# DAC_and_amp.net
KiCad netlist of a schematic drawn in Altium Designer
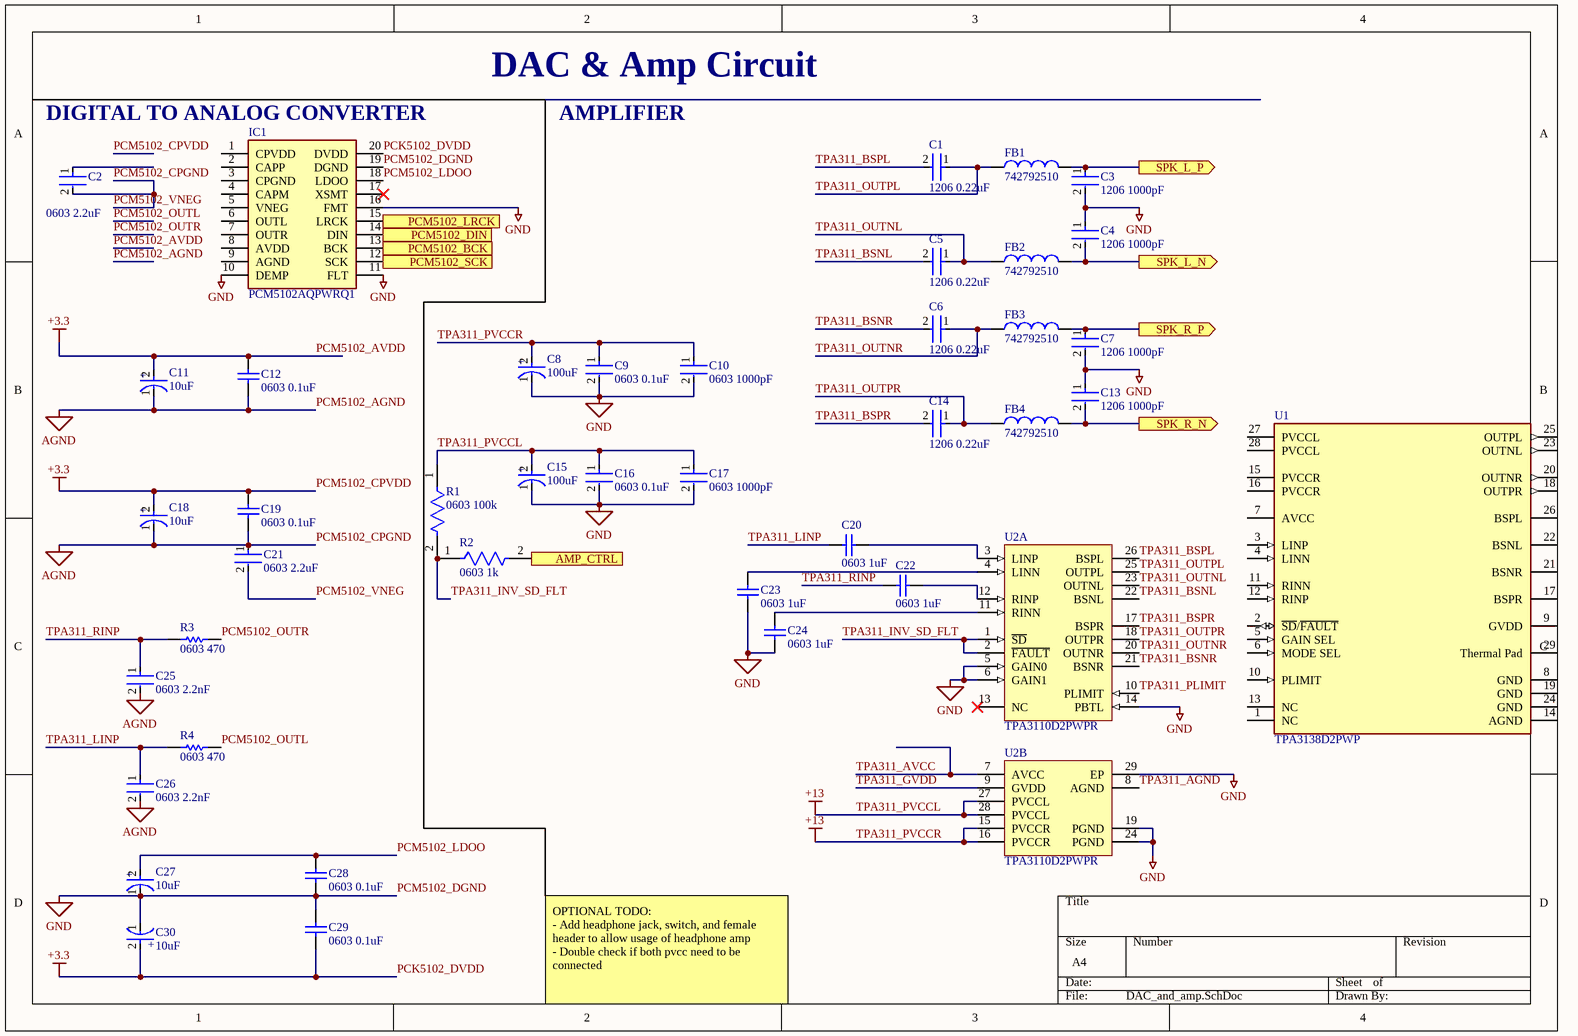
[diagram p0: DAC_and_amp.SchDoc]

(export (version "E")
  (design (tool "Eeschema 10.0.6"))
  (components
    (comp (ref "C1")
      (value "1206 0.22uF")
      (footprint "FP-C1206C-EB-MFG")
      (description "CAP CER 0.22UF 50V X7R 1206")
      (fields
        (field (name "OCTOPART") "https://octopart.com/c1206c224k5ractu-kemet-99129")
        (field (name "MANUFACTURER PART NUMBER") "C1206C224K5RACTU")
      )
      (libsource (lib "Altium Content Vault") (part "b4654b650e69147ec39a6b967a45e02"))
    )
    (comp (ref "C2")
      (value "0603 2.2uF")
      (footprint "FP-GRM188-0_1-e0_2_0_5-MFG")
      (description "Chip Multilayer Ceramic Capacitors for General Purpose, 0603, 2.2uF, X7R, 15%, 10%, 10V")
      (fields (field (name "VOLTAGE") "10V") (field (name "TOLERANCE") "10%"))
      (libsource (lib "Altium Content Vault") (part "11868f565c42a9108669ba33697ecf6"))
    )
    (comp (ref "C3")
      (value "1206 1000pF")
      (footprint "FP-C1206C-EB-MFG")
      (description "CAP CER 100PF 100V C0G/NP0 1206")
      (fields (field (name "MANUFACTURER") "KEMET") (field (name "TOLERANCE") "0.05"))
      (libsource (lib "Altium Content Vault") (part "b4654b650e69147ec39a6b967a45e02"))
    )
    (comp (ref "C4")
      (value "1206 1000pF")
      (footprint "FP-C1206C-EB-MFG")
      (description "CAP CER 100PF 100V C0G/NP0 1206")
      (fields (field (name "MANUFACTURER") "KEMET") (field (name "TOLERANCE") "0.05"))
      (libsource (lib "Altium Content Vault") (part "b4654b650e69147ec39a6b967a45e02"))
    )
    (comp (ref "C5")
      (value "1206 0.22uF")
      (footprint "FP-C1206C-EB-MFG")
      (description "CAP CER 0.22UF 50V X7R 1206")
      (fields
        (field (name "OCTOPART") "https://octopart.com/c1206c224k5ractu-kemet-99129")
        (field (name "MANUFACTURER PART NUMBER") "C1206C224K5RACTU")
      )
      (libsource (lib "Altium Content Vault") (part "b4654b650e69147ec39a6b967a45e02"))
    )
    (comp (ref "C6")
      (value "1206 0.22uF")
      (footprint "FP-C1206C-EB-MFG")
      (description "CAP CER 0.22UF 50V X7R 1206")
      (fields
        (field (name "OCTOPART") "https://octopart.com/c1206c224k5ractu-kemet-99129")
        (field (name "MANUFACTURER PART NUMBER") "C1206C224K5RACTU")
      )
      (libsource (lib "Altium Content Vault") (part "b4654b650e69147ec39a6b967a45e02"))
    )
    (comp (ref "C7")
      (value "1206 1000pF")
      (footprint "FP-C1206C-EB-MFG")
      (description "CAP CER 100PF 100V C0G/NP0 1206")
      (fields (field (name "MANUFACTURER") "KEMET") (field (name "TOLERANCE") "0.05"))
      (libsource (lib "Altium Content Vault") (part "b4654b650e69147ec39a6b967a45e02"))
    )
    (comp (ref "C8")
      (value "100uF")
      (footprint "FP-RAD-TH-D_8_0_5-L_11_5-MFG")
      (description "Aluminum Electrolytic Capacitors (Radial Lead Type) 100uF ±20% 50V")
      (fields (field (name "VOLTAGE") "50V") (field (name "TOLERANCE") "20%"))
      (libsource (lib "Altium Content Vault") (part "a00bbbee19879c290e62620ae7e47b1"))
    )
    (comp (ref "C9")
      (value "0603 0.1uF")
      (footprint "FP-C0603C-CF-MFG")
      (description "C0603 0.10 μF X7R 30ppm/°C 10.00% 25 V")
      (fields (field (name "MANUFACTURER PART NUMBER") "C0603C104K3RACTU"))
      (libsource (lib "Altium Content Vault") (part "b4654b650e69147ec39a6b967a45e02"))
    )
    (comp (ref "C10")
      (value "0603 1000pF")
      (footprint "FP-C0603C-CF-MFG")
      (description "C0603 1,000 pF C0G 30ppm/°C 5.00% 25 V")
      (fields (field (name "OCTOPART") "https://octopart.com/c0603c102j3gactu-kemet-8375722"))
      (libsource (lib "Altium Content Vault") (part "b4654b650e69147ec39a6b967a45e02"))
    )
    (comp (ref "C11")
      (value "10uF")
      (footprint "FP-35ZLH330MEFC10X12_5-MFG")
      (fields (field (name "TOLERANCE") "20%") (field (name "VOLTAGE") "35V"))
      (libsource (lib "Altium Content Vault") (part "a00bbbee19879c290e62620ae7e47b1"))
    )
    (comp (ref "C12")
      (value "0603 0.1uF")
      (footprint "CAPC1608X90X35ML10T15")
      (description "Chip Capacitor, 0.1 uF, +/- 10%, 50 V, -55 to 125 degC, 0603 (1608 Metric), RoHS, Tape and Reel")
      (fields (field (name "TOLERANCE") "10%") (field (name "VOLTAGE") "50V"))
      (libsource (lib "Altium Content Vault") (part "CAP-NP-2"))
    )
    (comp (ref "C13")
      (value "1206 1000pF")
      (footprint "FP-C1206C-EB-MFG")
      (description "CAP CER 100PF 100V C0G/NP0 1206")
      (fields (field (name "MANUFACTURER") "KEMET") (field (name "TOLERANCE") "0.05"))
      (libsource (lib "Altium Content Vault") (part "b4654b650e69147ec39a6b967a45e02"))
    )
    (comp (ref "C14")
      (value "1206 0.22uF")
      (footprint "FP-C1206C-EB-MFG")
      (description "CAP CER 0.22UF 50V X7R 1206")
      (fields
        (field (name "OCTOPART") "https://octopart.com/c1206c224k5ractu-kemet-99129")
        (field (name "MANUFACTURER PART NUMBER") "C1206C224K5RACTU")
      )
      (libsource (lib "Altium Content Vault") (part "b4654b650e69147ec39a6b967a45e02"))
    )
    (comp (ref "C15")
      (value "100uF")
      (footprint "FP-RAD-TH-D_8_0_5-L_11_5-MFG")
      (description "Aluminum Electrolytic Capacitors (Radial Lead Type) 100uF ±20% 50V")
      (fields (field (name "VOLTAGE") "50V") (field (name "TOLERANCE") "20%"))
      (libsource (lib "Altium Content Vault") (part "a00bbbee19879c290e62620ae7e47b1"))
    )
    (comp (ref "C16")
      (value "0603 0.1uF")
      (footprint "FP-C0603C-CF-MFG")
      (description "C0603 0.10 μF X7R 30ppm/°C 10.00% 25 V")
      (fields (field (name "MANUFACTURER PART NUMBER") "C0603C104K3RACTU"))
      (libsource (lib "Altium Content Vault") (part "b4654b650e69147ec39a6b967a45e02"))
    )
    (comp (ref "C17")
      (value "0603 1000pF")
      (footprint "FP-C0603C-CF-MFG")
      (description "C0603 1,000 pF C0G 30ppm/°C 5.00% 25 V")
      (fields (field (name "OCTOPART") "https://octopart.com/c0603c102j3gactu-kemet-8375722"))
      (libsource (lib "Altium Content Vault") (part "b4654b650e69147ec39a6b967a45e02"))
    )
    (comp (ref "C18")
      (value "10uF")
      (footprint "FP-35ZLH330MEFC10X12_5-MFG")
      (fields (field (name "TOLERANCE") "20%") (field (name "VOLTAGE") "35V"))
      (libsource (lib "Altium Content Vault") (part "a00bbbee19879c290e62620ae7e47b1"))
    )
    (comp (ref "C19")
      (value "0603 0.1uF")
      (footprint "CAPC1608X90X35ML10T15")
      (description "Chip Capacitor, 0.1 uF, +/- 10%, 50 V, -55 to 125 degC, 0603 (1608 Metric), RoHS, Tape and Reel")
      (fields (field (name "TOLERANCE") "10%") (field (name "VOLTAGE") "50V"))
      (libsource (lib "Altium Content Vault") (part "CAP-NP-2"))
    )
    (comp (ref "C20")
      (value "0603 1uF")
      (footprint "CAPC1608X87X35LL15T15")
      (fields (field (name "PART NUMBER") "C0603C105K3RACTU") (field (name "MANUFACTURER") "Kemet"))
      (libsource (lib "Altium Content Vault") (part "CAP"))
    )
    (comp (ref "C21")
      (value "0603 2.2uF")
      (footprint "FP-GRM188-0_1-e0_2_0_5-MFG")
      (description "Chip Multilayer Ceramic Capacitors for General Purpose, 0603, 2.2uF, X7R, 15%, 10%, 10V")
      (fields (field (name "VOLTAGE") "10V") (field (name "TOLERANCE") "10%"))
      (libsource (lib "Altium Content Vault") (part "11868f565c42a9108669ba33697ecf6"))
    )
    (comp (ref "C22")
      (value "0603 1uF")
      (footprint "CAPC1608X87X35LL15T15")
      (fields (field (name "PART NUMBER") "C0603C105K3RACTU") (field (name "MANUFACTURER") "Kemet"))
      (libsource (lib "Altium Content Vault") (part "CAP"))
    )
    (comp (ref "C23")
      (value "0603 1uF")
      (footprint "CAPC1608X87X35LL15T15")
      (fields (field (name "PART NUMBER") "C0603C105K3RACTU") (field (name "MANUFACTURER") "Kemet"))
      (libsource (lib "Altium Content Vault") (part "CAP"))
    )
    (comp (ref "C24")
      (value "0603 1uF")
      (footprint "CAPC1608X87X35LL15T15")
      (fields (field (name "PART NUMBER") "C0603C105K3RACTU") (field (name "MANUFACTURER") "Kemet"))
      (libsource (lib "Altium Content Vault") (part "CAP"))
    )
    (comp (ref "C25")
      (value "0603 2.2nF")
      (footprint "FP-GRM188-0_1-e0_2_0_5-MFG")
      (description "Chip Multilayer Ceramic Capacitors for General Purpose, 0603, 2200pF, C0G, 30ppm/°C, 5%, 50V")
      (fields (field (name "VOLTAGE") "50V") (field (name "TOLERANCE") "5%"))
      (libsource (lib "Altium Content Vault") (part "11868f565c42a9108669ba33697ecf6"))
    )
    (comp (ref "C26")
      (value "0603 2.2nF")
      (footprint "FP-GRM188-0_1-e0_2_0_5-MFG")
      (description "Chip Multilayer Ceramic Capacitors for General Purpose, 0603, 2200pF, C0G, 30ppm/°C, 5%, 50V")
      (fields (field (name "VOLTAGE") "50V") (field (name "TOLERANCE") "5%"))
      (libsource (lib "Altium Content Vault") (part "11868f565c42a9108669ba33697ecf6"))
    )
    (comp (ref "C27")
      (value "10uF")
      (footprint "FP-35ZLH330MEFC10X12_5-MFG")
      (fields (field (name "TOLERANCE") "20%") (field (name "VOLTAGE") "35V"))
      (libsource (lib "Altium Content Vault") (part "a00bbbee19879c290e62620ae7e47b1"))
    )
    (comp (ref "C28")
      (value "0603 0.1uF")
      (footprint "CAPC1608X90X35ML10T15")
      (description "Chip Capacitor, 0.1 uF, +/- 10%, 50 V, -55 to 125 degC, 0603 (1608 Metric), RoHS, Tape and Reel")
      (fields (field (name "TOLERANCE") "10%") (field (name "VOLTAGE") "50V"))
      (libsource (lib "Altium Content Vault") (part "CAP-NP-2"))
    )
    (comp (ref "C29")
      (value "0603 0.1uF")
      (footprint "CAPC1608X90X35ML10T15")
      (description "Chip Capacitor, 0.1 uF, +/- 10%, 50 V, -55 to 125 degC, 0603 (1608 Metric), RoHS, Tape and Reel")
      (fields (field (name "TOLERANCE") "10%") (field (name "VOLTAGE") "50V"))
      (libsource (lib "Altium Content Vault") (part "CAP-NP-2"))
    )
    (comp (ref "C30")
      (value "10uF")
      (footprint "FP-35ZLH330MEFC10X12_5-MFG")
      (fields (field (name "TOLERANCE") "20%") (field (name "VOLTAGE") "35V"))
      (libsource (lib "Altium Content Vault") (part "a00bbbee19879c290e62620ae7e47b1"))
    )
    (comp (ref "FB1")
      (value "742792510")
      (footprint "WE-CBF_1812_L4.5W3.2H1.5_HC")
      (fields (field (name "TOLERANCE") "25%"))
      (libsource (lib "Altium Content Vault") (part "Ferrite"))
    )
    (comp (ref "FB2")
      (value "742792510")
      (footprint "WE-CBF_1812_L4.5W3.2H1.5_HC")
      (fields (field (name "TOLERANCE") "25%"))
      (libsource (lib "Altium Content Vault") (part "Ferrite"))
    )
    (comp (ref "FB3")
      (value "742792510")
      (footprint "WE-CBF_1812_L4.5W3.2H1.5_HC")
      (fields (field (name "TOLERANCE") "25%"))
      (libsource (lib "Altium Content Vault") (part "Ferrite"))
    )
    (comp (ref "FB4")
      (value "742792510")
      (footprint "WE-CBF_1812_L4.5W3.2H1.5_HC")
      (fields (field (name "TOLERANCE") "25%"))
      (libsource (lib "Altium Content Vault") (part "Ferrite"))
    )
    (comp (ref "IC1")
      (value "PCM5102AQPWRQ1")
      (footprint "SamacSys:SOP65P640X120-20N")
      (description "Integrated Circuit")
      (fields (field (name "MOUSER PART NUMBER") "595-PCM5102AQPWRQ1"))
      (libsource (lib "*") (part "PCM5102AQPWRQ1"))
    )
    (comp (ref "R1")
      (value "0603 100k")
      (footprint "FP-RC0603-0_55-MFG")
      (description "RES SMD 100K OHM 1% 1/10W 0603")
      (fields (field (name "TOLERANCE") "1%"))
      (libsource (lib "Altium Content Vault") (part "1029c3af85768c4190bb7ad29bc67b5"))
    )
    (comp (ref "R2")
      (value "0603 1k")
      (footprint "FP-AC0603-IPC_B")
      (description "RES 1kΩ 1.00% 0.1W 0603")
      (fields (field (name "TOLERANCE") "1%"))
      (libsource (lib "Altium Content Vault") (part "1029c3af85768c4190bb7ad29bc67b5"))
    )
    (comp (ref "R3")
      (value "0603 470")
      (footprint "RESC1608X55X30NL15T15")
      (fields (field (name "PART NUMBER") "ERJ-3GEYJ471V") (field (name "MANUFACTURER") "Panasonic"))
      (libsource (lib "Altium Content Vault") (part "RES"))
    )
    (comp (ref "R4")
      (value "0603 470")
      (footprint "RESC1608X55X30NL15T15")
      (fields (field (name "PART NUMBER") "ERJ-3GEYJ471V") (field (name "MANUFACTURER") "Panasonic"))
      (libsource (lib "Altium Content Vault") (part "RES"))
    )
    (comp (ref "U1")
      (value "TPA3138D2PWP")
      (footprint "FP-PWP0028H-IPC_B")
      (description "IC AMP D MON/STER 18.5W 28HTSSOP")
      (libsource (lib "Altium Content Vault") (part "b1a8bcd8ca7e070d33af0525e816573"))
    )
    (comp (ref "U2")
      (value "TPA3110D2PWPR")
      (footprint "TI-PWP28-5720X1950TP_L")
      (fields (field (name "MANUFACTURER") "Texas Instruments"))
      (libsource (lib "Altium Content Vault") (part "TI-TPA311XD2PWP28-6240X1950TP"))
    )
  )
  (nets
    (net (code "1") (name "+3.3") (class "Default")
      (node (ref "C11") (pin "2") (pinfunction "A_2") (pintype "passive"))
      (node (ref "C12") (pin "2") (pinfunction "2_2") (pintype "passive"))
      (node (ref "C18") (pin "2") (pinfunction "A_2") (pintype "passive"))
      (node (ref "C19") (pin "2") (pinfunction "2_2") (pintype "passive"))
      (node (ref "C29") (pin "1") (pinfunction "1_1") (pintype "passive"))
      (node (ref "C30") (pin "2") (pinfunction "A_2") (pintype "passive"))
      (node (ref "IC1") (pin "20") (pinfunction "DVDD_20") (pintype "passive"))
    )
    (net (code "2") (name "+13") (class "Default")
      (node (ref "C10") (pin "1") (pinfunction "1_1") (pintype "passive"))
      (node (ref "C15") (pin "2") (pinfunction "A_2") (pintype "passive"))
      (node (ref "C16") (pin "1") (pinfunction "1_1") (pintype "passive"))
      (node (ref "C17") (pin "1") (pinfunction "1_1") (pintype "passive"))
      (node (ref "C8") (pin "2") (pinfunction "A_2") (pintype "passive"))
      (node (ref "C9") (pin "1") (pinfunction "1_1") (pintype "passive"))
      (node (ref "R1") (pin "1") (pinfunction "1_1") (pintype "passive"))
      (node (ref "U2") (pin "15") (pinfunction "PVCCR_15") (pintype "power_in"))
      (node (ref "U2") (pin "16") (pinfunction "PVCCR_16") (pintype "power_in"))
      (node (ref "U2") (pin "27") (pinfunction "PVCCL_27") (pintype "power_in"))
      (node (ref "U2") (pin "28") (pinfunction "PVCCL_28") (pintype "power_in"))
    )
    (net (code "3") (name "/AMP_CTRL") (class "Default")
      (node (ref "R2") (pin "2") (pinfunction "2_2") (pintype "passive"))
    )
    (net (code "4") (name "/PCM5102_BCK") (class "Default")
      (node (ref "IC1") (pin "13") (pinfunction "BCK_13") (pintype "passive"))
    )
    (net (code "5") (name "/PCM5102_DIN") (class "Default")
      (node (ref "IC1") (pin "14") (pinfunction "DIN_14") (pintype "passive"))
    )
    (net (code "6") (name "/PCM5102_LDOO") (class "Default")
      (node (ref "C27") (pin "2") (pinfunction "A_2") (pintype "passive"))
      (node (ref "C28") (pin "2") (pinfunction "2_2") (pintype "passive"))
      (node (ref "IC1") (pin "18") (pinfunction "LDOO_18") (pintype "passive"))
    )
    (net (code "7") (name "/PCM5102_LRCK") (class "Default")
      (node (ref "IC1") (pin "15") (pinfunction "LRCK_15") (pintype "passive"))
    )
    (net (code "8") (name "/PCM5102_OUTL") (class "Default")
      (node (ref "R4") (pin "2") (pinfunction "2_2") (pintype "passive"))
    )
    (net (code "9") (name "/PCM5102_OUTR") (class "Default")
      (node (ref "R3") (pin "2") (pinfunction "2_2") (pintype "passive"))
    )
    (net (code "10") (name "/PCM5102_SCK") (class "Default")
      (node (ref "IC1") (pin "12") (pinfunction "SCK_12") (pintype "passive"))
    )
    (net (code "11") (name "/SPK_L_N") (class "Default")
      (node (ref "C4") (pin "2") (pinfunction "2_2") (pintype "passive"))
      (node (ref "FB2") (pin "2") (pinfunction "2_2") (pintype "passive"))
    )
    (net (code "12") (name "/SPK_L_P") (class "Default")
      (node (ref "C3") (pin "1") (pinfunction "1_1") (pintype "passive"))
      (node (ref "FB1") (pin "2") (pinfunction "2_2") (pintype "passive"))
    )
    (net (code "13") (name "/SPK_R_N") (class "Default")
      (node (ref "C13") (pin "2") (pinfunction "2_2") (pintype "passive"))
      (node (ref "FB4") (pin "2") (pinfunction "2_2") (pintype "passive"))
    )
    (net (code "14") (name "/SPK_R_P") (class "Default")
      (node (ref "C7") (pin "1") (pinfunction "1_1") (pintype "passive"))
      (node (ref "FB3") (pin "2") (pinfunction "2_2") (pintype "passive"))
    )
    (net (code "15") (name "/TPA311_AGND") (class "Default")
      (node (ref "U2") (pin "8") (pinfunction "AGND_8") (pintype "power_in"))
    )
    (net (code "16") (name "/TPA311_AVCC") (class "Default")
      (node (ref "U2") (pin "7") (pinfunction "AVCC_7") (pintype "power_in"))
    )
    (net (code "17") (name "/TPA311_BSNL") (class "Default")
      (node (ref "C5") (pin "2") (pinfunction "2_2") (pintype "passive"))
      (node (ref "U2") (pin "22") (pinfunction "BSNL_22") (pintype "passive"))
    )
    (net (code "18") (name "/TPA311_BSNR") (class "Default")
      (node (ref "C6") (pin "2") (pinfunction "2_2") (pintype "passive"))
      (node (ref "U2") (pin "21") (pinfunction "BSNR_21") (pintype "passive"))
    )
    (net (code "19") (name "/TPA311_BSPL") (class "Default")
      (node (ref "C1") (pin "2") (pinfunction "2_2") (pintype "passive"))
      (node (ref "U2") (pin "26") (pinfunction "BSPL_26") (pintype "passive"))
    )
    (net (code "20") (name "/TPA311_BSPR") (class "Default")
      (node (ref "C14") (pin "2") (pinfunction "2_2") (pintype "passive"))
      (node (ref "U2") (pin "17") (pinfunction "BSPR_17") (pintype "passive"))
    )
    (net (code "21") (name "/TPA311_GVDD") (class "Default")
      (node (ref "U2") (pin "9") (pinfunction "GVDD_9") (pintype "power_in"))
    )
    (net (code "22") (name "/TPA311_INV_SD_FLT") (class "Default")
      (node (ref "R1") (pin "2") (pinfunction "2_2") (pintype "passive"))
      (node (ref "R2") (pin "1") (pinfunction "1_1") (pintype "passive"))
      (node (ref "U2") (pin "1") (pinfunction "~{SD}_1") (pintype "input"))
      (node (ref "U2") (pin "2") (pinfunction "~{FAULT}_2") (pintype "open_collector"))
    )
    (net (code "23") (name "/TPA311_LINP") (class "Default")
      (node (ref "C20") (pin "1") (pinfunction "1_1") (pintype "passive"))
      (node (ref "C26") (pin "1") (pinfunction "1_1") (pintype "passive"))
      (node (ref "R4") (pin "1") (pinfunction "1_1") (pintype "passive"))
    )
    (net (code "24") (name "/TPA311_OUTNL") (class "Default")
      (node (ref "C5") (pin "1") (pinfunction "1_1") (pintype "passive"))
      (node (ref "FB2") (pin "1") (pinfunction "1_1") (pintype "passive"))
      (node (ref "U2") (pin "23") (pinfunction "OUTNL_23") (pintype "tri_state"))
    )
    (net (code "25") (name "/TPA311_OUTNR") (class "Default")
      (node (ref "C6") (pin "1") (pinfunction "1_1") (pintype "passive"))
      (node (ref "FB3") (pin "1") (pinfunction "1_1") (pintype "passive"))
      (node (ref "U2") (pin "20") (pinfunction "OUTNR_20") (pintype "tri_state"))
    )
    (net (code "26") (name "/TPA311_OUTPL") (class "Default")
      (node (ref "C1") (pin "1") (pinfunction "1_1") (pintype "passive"))
      (node (ref "FB1") (pin "1") (pinfunction "1_1") (pintype "passive"))
      (node (ref "U2") (pin "25") (pinfunction "OUTPL_25") (pintype "tri_state"))
    )
    (net (code "27") (name "/TPA311_OUTPR") (class "Default")
      (node (ref "C14") (pin "1") (pinfunction "1_1") (pintype "passive"))
      (node (ref "FB4") (pin "1") (pinfunction "1_1") (pintype "passive"))
      (node (ref "U2") (pin "18") (pinfunction "OUTPR_18") (pintype "tri_state"))
    )
    (net (code "28") (name "/TPA311_PLIMIT") (class "Default")
      (node (ref "U2") (pin "10") (pinfunction "PLIMIT_10") (pintype "input"))
    )
    (net (code "29") (name "/TPA311_RINP") (class "Default")
      (node (ref "C22") (pin "1") (pinfunction "1_1") (pintype "passive"))
      (node (ref "C25") (pin "1") (pinfunction "1_1") (pintype "passive"))
      (node (ref "R3") (pin "1") (pinfunction "1_1") (pintype "passive"))
    )
    (net (code "30") (name "AGND") (class "Default")
      (node (ref "C11") (pin "1") (pinfunction "C_1") (pintype "passive"))
      (node (ref "C12") (pin "1") (pinfunction "1_1") (pintype "passive"))
      (node (ref "C18") (pin "1") (pinfunction "C_1") (pintype "passive"))
      (node (ref "C19") (pin "1") (pinfunction "1_1") (pintype "passive"))
      (node (ref "C2") (pin "2") (pinfunction "2_2") (pintype "passive"))
      (node (ref "C21") (pin "1") (pinfunction "1_1") (pintype "passive"))
      (node (ref "C21") (pin "2") (pinfunction "2_2") (pintype "passive"))
      (node (ref "C25") (pin "2") (pinfunction "2_2") (pintype "passive"))
      (node (ref "C26") (pin "2") (pinfunction "2_2") (pintype "passive"))
    )
    (net (code "31") (name "GND") (class "Default")
      (node (ref "C10") (pin "2") (pinfunction "2_2") (pintype "passive"))
      (node (ref "C13") (pin "1") (pinfunction "1_1") (pintype "passive"))
      (node (ref "C15") (pin "1") (pinfunction "C_1") (pintype "passive"))
      (node (ref "C16") (pin "2") (pinfunction "2_2") (pintype "passive"))
      (node (ref "C17") (pin "2") (pinfunction "2_2") (pintype "passive"))
      (node (ref "C23") (pin "1") (pinfunction "1_1") (pintype "passive"))
      (node (ref "C24") (pin "1") (pinfunction "1_1") (pintype "passive"))
      (node (ref "C27") (pin "1") (pinfunction "C_1") (pintype "passive"))
      (node (ref "C28") (pin "1") (pinfunction "1_1") (pintype "passive"))
      (node (ref "C29") (pin "2") (pinfunction "2_2") (pintype "passive"))
      (node (ref "C3") (pin "2") (pinfunction "2_2") (pintype "passive"))
      (node (ref "C30") (pin "1") (pinfunction "C_1") (pintype "passive"))
      (node (ref "C4") (pin "1") (pinfunction "1_1") (pintype "passive"))
      (node (ref "C7") (pin "2") (pinfunction "2_2") (pintype "passive"))
      (node (ref "C8") (pin "1") (pinfunction "C_1") (pintype "passive"))
      (node (ref "C9") (pin "2") (pinfunction "2_2") (pintype "passive"))
      (node (ref "IC1") (pin "10") (pinfunction "DEMP_10") (pintype "passive"))
      (node (ref "IC1") (pin "11") (pinfunction "FLT_11") (pintype "passive"))
      (node (ref "IC1") (pin "16") (pinfunction "FMT_16") (pintype "passive"))
      (node (ref "IC1") (pin "19") (pinfunction "DGND_19") (pintype "passive"))
      (node (ref "U2") (pin "14") (pinfunction "PBTL_14") (pintype "input"))
      (node (ref "U2") (pin "19") (pinfunction "PGND_19") (pintype "power_in"))
      (node (ref "U2") (pin "24") (pinfunction "PGND_24") (pintype "power_in"))
      (node (ref "U2") (pin "29") (pinfunction "EP_29") (pintype "power_in"))
      (node (ref "U2") (pin "5") (pinfunction "GAIN0_5") (pintype "input"))
      (node (ref "U2") (pin "6") (pinfunction "GAIN1_6") (pintype "input"))
    )
    (net (code "32") (name "Net-(U2A-LINN)") (class "Default")
      (node (ref "C23") (pin "2") (pinfunction "2_2") (pintype "passive"))
      (node (ref "U2") (pin "4") (pinfunction "LINN_4") (pintype "input"))
    )
    (net (code "33") (name "Net-(U2A-LINP)") (class "Default")
      (node (ref "C20") (pin "2") (pinfunction "2_2") (pintype "passive"))
      (node (ref "U2") (pin "3") (pinfunction "LINP_3") (pintype "input"))
    )
    (net (code "34") (name "Net-(U2A-RINN)") (class "Default")
      (node (ref "C24") (pin "2") (pinfunction "2_2") (pintype "passive"))
      (node (ref "U2") (pin "11") (pinfunction "RINN_11") (pintype "input"))
    )
    (net (code "35") (name "Net-(U2A-RINP)") (class "Default")
      (node (ref "C22") (pin "2") (pinfunction "2_2") (pintype "passive"))
      (node (ref "U2") (pin "12") (pinfunction "RINP_12") (pintype "input"))
    )
    (net (code "36") (name "unconnected-(C2-Pad1)") (class "Default")
      (node (ref "C2") (pin "1") (pinfunction "1_1") (pintype "passive"))
    )
    (net (code "37") (name "unconnected-(IC1-AGND-Pad9)") (class "Default")
      (node (ref "IC1") (pin "9") (pinfunction "AGND_9") (pintype "passive"))
    )
    (net (code "38") (name "unconnected-(IC1-AVDD-Pad8)") (class "Default")
      (node (ref "IC1") (pin "8") (pinfunction "AVDD_8") (pintype "passive"))
    )
    (net (code "39") (name "unconnected-(IC1-CAPM-Pad4)") (class "Default")
      (node (ref "IC1") (pin "4") (pinfunction "CAPM_4") (pintype "passive"))
    )
    (net (code "40") (name "unconnected-(IC1-CAPP-Pad2)") (class "Default")
      (node (ref "IC1") (pin "2") (pinfunction "CAPP_2") (pintype "passive"))
    )
    (net (code "41") (name "unconnected-(IC1-CPGND-Pad3)") (class "Default")
      (node (ref "IC1") (pin "3") (pinfunction "CPGND_3") (pintype "passive"))
    )
    (net (code "42") (name "unconnected-(IC1-CPVDD-Pad1)") (class "Default")
      (node (ref "IC1") (pin "1") (pinfunction "CPVDD_1") (pintype "passive"))
    )
    (net (code "43") (name "unconnected-(IC1-OUTL-Pad6)") (class "Default")
      (node (ref "IC1") (pin "6") (pinfunction "OUTL_6") (pintype "passive"))
    )
    (net (code "44") (name "unconnected-(IC1-OUTR-Pad7)") (class "Default")
      (node (ref "IC1") (pin "7") (pinfunction "OUTR_7") (pintype "passive"))
    )
    (net (code "45") (name "unconnected-(IC1-VNEG-Pad5)") (class "Default")
      (node (ref "IC1") (pin "5") (pinfunction "VNEG_5") (pintype "passive"))
    )
    (net (code "46") (name "unconnected-(IC1-XSMT-Pad17)") (class "Default")
      (node (ref "IC1") (pin "17") (pinfunction "XSMT_17") (pintype "passive+no_connect"))
    )
    (net (code "47") (name "unconnected-(U1-AGND-Pad14)") (class "Default")
      (node (ref "U1") (pin "14") (pinfunction "AGND_14") (pintype "power_in"))
    )
    (net (code "48") (name "unconnected-(U1-AVCC-Pad7)") (class "Default")
      (node (ref "U1") (pin "7") (pinfunction "AVCC_7") (pintype "power_in"))
    )
    (net (code "49") (name "unconnected-(U1-BSNL-Pad22)") (class "Default")
      (node (ref "U1") (pin "22") (pinfunction "BSNL_22") (pintype "power_in"))
    )
    (net (code "50") (name "unconnected-(U1-BSNR-Pad21)") (class "Default")
      (node (ref "U1") (pin "21") (pinfunction "BSNR_21") (pintype "power_in"))
    )
    (net (code "51") (name "unconnected-(U1-BSPL-Pad26)") (class "Default")
      (node (ref "U1") (pin "26") (pinfunction "BSPL_26") (pintype "power_in"))
    )
    (net (code "52") (name "unconnected-(U1-BSPR-Pad17)") (class "Default")
      (node (ref "U1") (pin "17") (pinfunction "BSPR_17") (pintype "power_in"))
    )
    (net (code "53") (name "unconnected-(U1-GAIN_SEL-Pad5)") (class "Default")
      (node (ref "U1") (pin "5") (pinfunction "GAIN_SEL_5") (pintype "input"))
    )
    (net (code "54") (name "unconnected-(U1-GND-Pad8)") (class "Default")
      (node (ref "U1") (pin "8") (pinfunction "GND_8") (pintype "power_in"))
    )
    (net (code "55") (name "unconnected-(U1-GND-Pad19)") (class "Default")
      (node (ref "U1") (pin "19") (pinfunction "GND_19") (pintype "power_in"))
    )
    (net (code "56") (name "unconnected-(U1-GND-Pad24)") (class "Default")
      (node (ref "U1") (pin "24") (pinfunction "GND_24") (pintype "power_in"))
    )
    (net (code "57") (name "unconnected-(U1-GVDD-Pad9)") (class "Default")
      (node (ref "U1") (pin "9") (pinfunction "GVDD_9") (pintype "power_in"))
    )
    (net (code "58") (name "unconnected-(U1-LINN-Pad4)") (class "Default")
      (node (ref "U1") (pin "4") (pinfunction "LINN_4") (pintype "input"))
    )
    (net (code "59") (name "unconnected-(U1-LINP-Pad3)") (class "Default")
      (node (ref "U1") (pin "3") (pinfunction "LINP_3") (pintype "input"))
    )
    (net (code "60") (name "unconnected-(U1-MODE_SEL-Pad6)") (class "Default")
      (node (ref "U1") (pin "6") (pinfunction "MODE_SEL_6") (pintype "input"))
    )
    (net (code "61") (name "unconnected-(U1-NC-Pad1)") (class "Default")
      (node (ref "U1") (pin "1") (pinfunction "NC_1") (pintype "passive"))
    )
    (net (code "62") (name "unconnected-(U1-NC-Pad13)") (class "Default")
      (node (ref "U1") (pin "13") (pinfunction "NC_13") (pintype "passive"))
    )
    (net (code "63") (name "unconnected-(U1-OUTNL-Pad23)") (class "Default")
      (node (ref "U1") (pin "23") (pinfunction "OUTNL_23") (pintype "output"))
    )
    (net (code "64") (name "unconnected-(U1-OUTNR-Pad20)") (class "Default")
      (node (ref "U1") (pin "20") (pinfunction "OUTNR_20") (pintype "output"))
    )
    (net (code "65") (name "unconnected-(U1-OUTPL-Pad25)") (class "Default")
      (node (ref "U1") (pin "25") (pinfunction "OUTPL_25") (pintype "output"))
    )
    (net (code "66") (name "unconnected-(U1-OUTPR-Pad18)") (class "Default")
      (node (ref "U1") (pin "18") (pinfunction "OUTPR_18") (pintype "output"))
    )
    (net (code "67") (name "unconnected-(U1-PLIMIT-Pad10)") (class "Default")
      (node (ref "U1") (pin "10") (pinfunction "PLIMIT_10") (pintype "input"))
    )
    (net (code "68") (name "unconnected-(U1-PVCCL-Pad27)") (class "Default")
      (node (ref "U1") (pin "27") (pinfunction "PVCCL_27") (pintype "power_in"))
    )
    (net (code "69") (name "unconnected-(U1-PVCCL-Pad28)") (class "Default")
      (node (ref "U1") (pin "28") (pinfunction "PVCCL_28") (pintype "power_in"))
    )
    (net (code "70") (name "unconnected-(U1-PVCCR-Pad15)") (class "Default")
      (node (ref "U1") (pin "15") (pinfunction "PVCCR_15") (pintype "power_in"))
    )
    (net (code "71") (name "unconnected-(U1-PVCCR-Pad16)") (class "Default")
      (node (ref "U1") (pin "16") (pinfunction "PVCCR_16") (pintype "power_in"))
    )
    (net (code "72") (name "unconnected-(U1-RINN-Pad11)") (class "Default")
      (node (ref "U1") (pin "11") (pinfunction "RINN_11") (pintype "input"))
    )
    (net (code "73") (name "unconnected-(U1-RINP-Pad12)") (class "Default")
      (node (ref "U1") (pin "12") (pinfunction "RINP_12") (pintype "input"))
    )
    (net (code "74") (name "unconnected-(U1-Thermal_Pad-Pad29)") (class "Default")
      (node (ref "U1") (pin "29") (pinfunction "Thermal_Pad_29") (pintype "power_in"))
    )
    (net (code "75") (name "unconnected-(U1-~{SD}{slash}~{FAULT}-Pad2)") (class "Default")
      (node (ref "U1") (pin "2") (pinfunction "~{SD}/~{FAULT}_2") (pintype "bidirectional"))
    )
    (net (code "76") (name "unconnected-(U2A-NC-Pad13)") (class "Default")
      (node (ref "U2") (pin "13") (pinfunction "NC_13") (pintype "passive+no_connect"))
    )
  )
)
